# 99.net
KiCad netlist of a schematic drawn in EAGLE
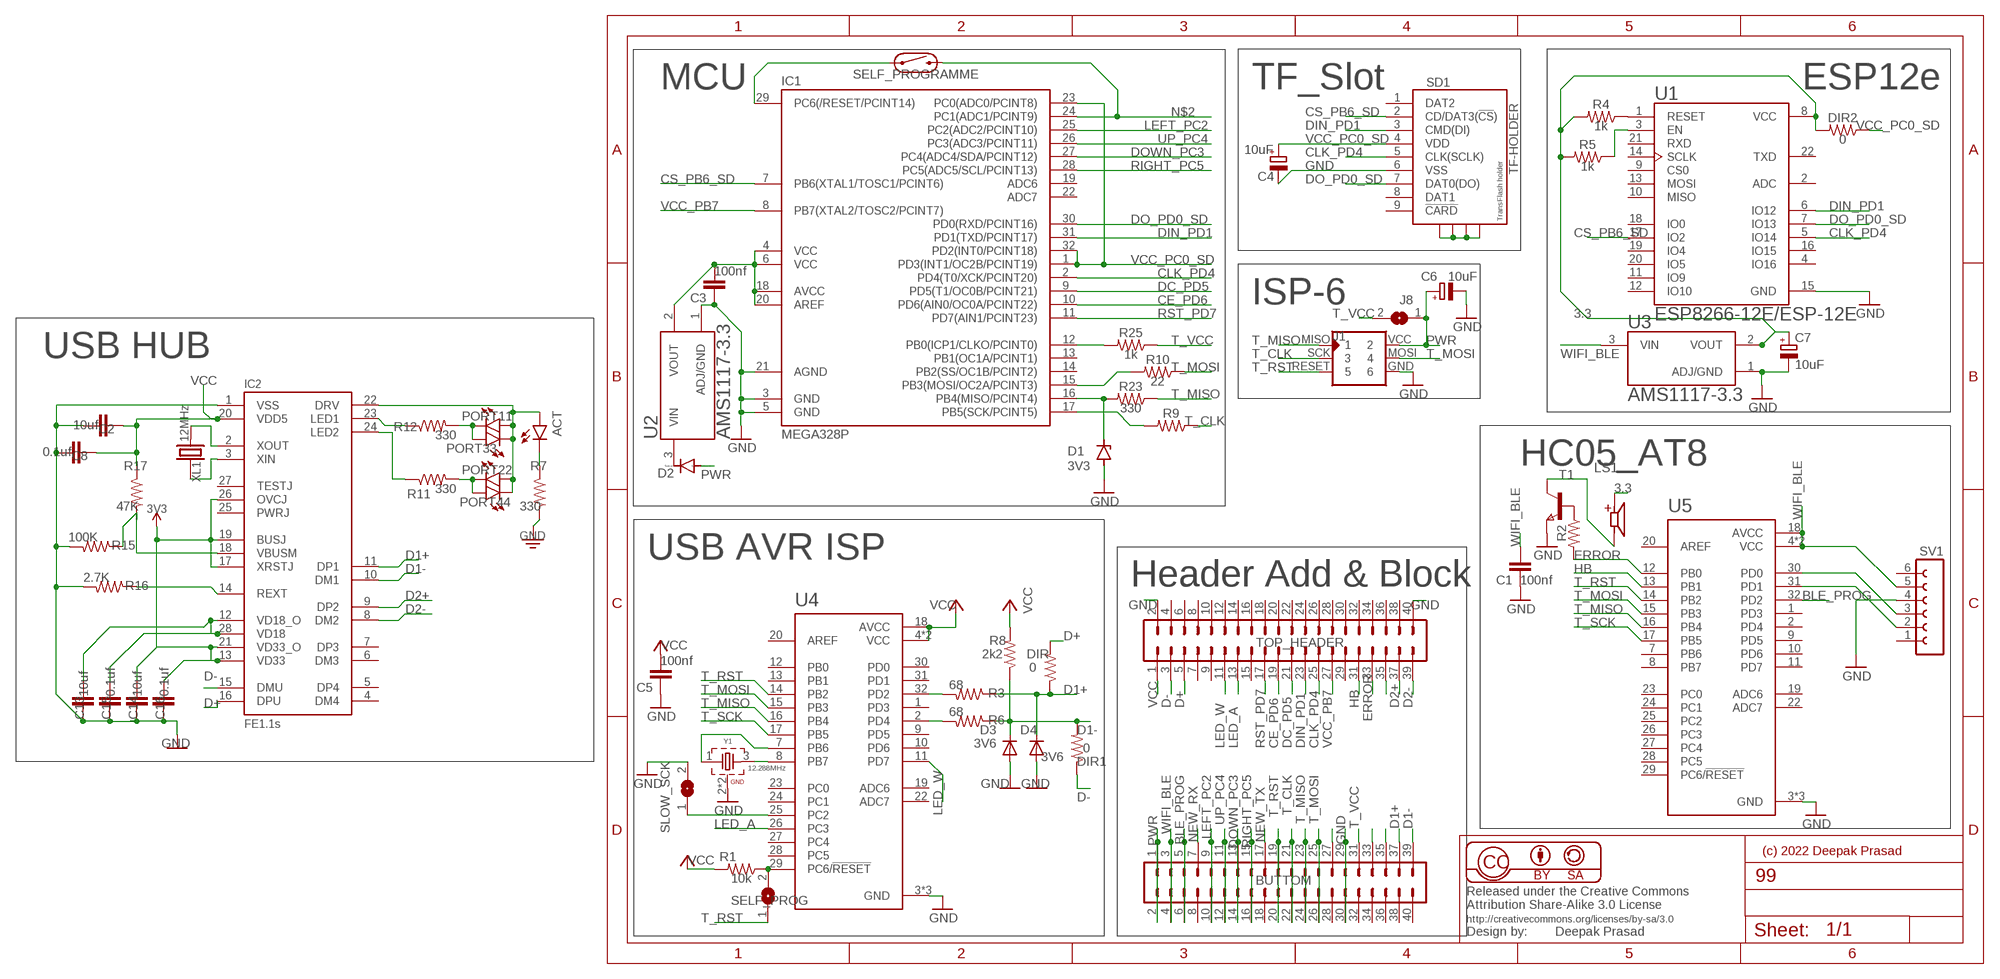
[diagram p0: schematic, sheet 1]

(export (version "E")
  (design (tool "Eeschema 10.0.6"))
  (components
    (comp (ref "ACT")
      (value "LED1206")
      (footprint "eagle-import:LED-1206")
      (libsource (lib "eagle-import") (part "LED1206"))
    )
    (comp (ref "BUTTOM")
      (value "MA20-2")
      (footprint "eagle-import:MA20-2")
      (libsource (lib "eagle-import") (part "MA20-2"))
    )
    (comp (ref "C1")
      (value "100nf")
      (footprint "eagle-import:C1206")
      (libsource (lib "eagle-import") (part "C-EUC1206"))
    )
    (comp (ref "C2")
      (value "10uf")
      (footprint "eagle-import:C1206")
      (libsource (lib "eagle-import") (part "C-EUC1206"))
    )
    (comp (ref "C3")
      (value "100nf")
      (footprint "eagle-import:C1206")
      (libsource (lib "eagle-import") (part "C-EUC1206"))
    )
    (comp (ref "C4")
      (value "10uF")
      (footprint "eagle-import:C_6032-28R")
      (libsource (lib "eagle-import") (part "CPOL-EUC/6032-28R"))
    )
    (comp (ref "C5")
      (value "100nf")
      (footprint "eagle-import:C1206")
      (libsource (lib "eagle-import") (part "C-EUC1206"))
    )
    (comp (ref "C6")
      (value "10uF")
      (footprint "eagle-import:C_6032-28R")
      (libsource (lib "eagle-import") (part "CPOL-EUC/6032-28R"))
    )
    (comp (ref "C7")
      (value "10uF")
      (footprint "eagle-import:C_6032-28R")
      (libsource (lib "eagle-import") (part "CPOL-EUC/6032-28R"))
    )
    (comp (ref "C8")
      (value "0.1uf")
      (footprint "eagle-import:C1206")
      (libsource (lib "eagle-import") (part "C-EUC1206"))
    )
    (comp (ref "C13")
      (value "10uf")
      (footprint "eagle-import:C1206")
      (libsource (lib "eagle-import") (part "C-EUC1206"))
    )
    (comp (ref "C14")
      (value "10uf")
      (footprint "eagle-import:C1206")
      (libsource (lib "eagle-import") (part "C-EUC1206"))
    )
    (comp (ref "C15")
      (value "0.1uf")
      (footprint "eagle-import:C1206")
      (libsource (lib "eagle-import") (part "C-EUC1206"))
    )
    (comp (ref "C16")
      (value "0.1uf")
      (footprint "eagle-import:C1206")
      (libsource (lib "eagle-import") (part "C-EUC1206"))
    )
    (comp (ref "D1")
      (value "3V3")
      (footprint "eagle-import:SOD80C")
      (libsource (lib "eagle-import") (part "ZENER-DIODESOD80C"))
    )
    (comp (ref "D2")
      (value "DIODE-DO214AC")
      (footprint "eagle-import:DO214AC")
      (libsource (lib "eagle-import") (part "DIODE-DO214AC"))
    )
    (comp (ref "D3")
      (value "3V6")
      (footprint "eagle-import:SMA-DIODE")
      (libsource (lib "eagle-import") (part "DIODESMA"))
    )
    (comp (ref "D4")
      (value "3V6")
      (footprint "eagle-import:SMA-DIODE")
      (libsource (lib "eagle-import") (part "DIODESMA"))
    )
    (comp (ref "DIR")
      (value "0")
      (footprint "eagle-import:RESC3216X70")
      (libsource (lib "eagle-import") (part "R-USCHIP-1206(3216-METRIC)_"))
    )
    (comp (ref "DIR1")
      (value "0")
      (footprint "eagle-import:RESC3216X70")
      (libsource (lib "eagle-import") (part "R-USCHIP-1206(3216-METRIC)_"))
    )
    (comp (ref "DIR2")
      (value "0")
      (footprint "eagle-import:RESC3216X70")
      (libsource (lib "eagle-import") (part "R-USCHIP-1206(3216-METRIC)_"))
    )
    (comp (ref "IC1")
      (value "MEGA328P")
      (footprint "eagle-import:TQFP32-08")
      (libsource (lib "eagle-import") (part "MEGA48/88/168-AU"))
    )
    (comp (ref "IC2")
      (value "FE1.1S")
      (footprint "eagle-import:FE1.1S_SSOP-28")
      (libsource (lib "eagle-import") (part "FE1.1S"))
    )
    (comp (ref "J1")
      (value "AVR-ISP-6PINAVR-ISP-6PIN")
      (footprint "eagle-import:AVR-ISP-6PIN")
      (libsource (lib "eagle-import") (part "AVR-ISP-6PINAVR-ISP-6PIN"))
    )
    (comp (ref "J8")
      (value "SJW")
      (footprint "eagle-import:SJW")
      (libsource (lib "eagle-import") (part "SJW"))
    )
    (comp (ref "LS1")
      (value "CMT-8530S-SMT")
      (footprint "eagle-import:CUI_CMT-8530S-SMT")
      (fields (field (name "MF") "CUI Devices") (field (name "MP") "CMT-8530S-SMT-TR"))
      (libsource (lib "eagle-import") (part "CMT-8530S-SMT"))
    )
    (comp (ref "PORT11")
      (value "LED1206")
      (footprint "eagle-import:LED-1206")
      (libsource (lib "eagle-import") (part "LED1206"))
    )
    (comp (ref "PORT22")
      (value "LED1206")
      (footprint "eagle-import:LED-1206")
      (libsource (lib "eagle-import") (part "LED1206"))
    )
    (comp (ref "PORT33")
      (value "LED1206")
      (footprint "eagle-import:LED-1206")
      (libsource (lib "eagle-import") (part "LED1206"))
    )
    (comp (ref "PORT44")
      (value "LED1206")
      (footprint "eagle-import:LED-1206")
      (libsource (lib "eagle-import") (part "LED1206"))
    )
    (comp (ref "R1")
      (value "10k")
      (footprint "eagle-import:RESC3216X70")
      (libsource (lib "eagle-import") (part "R-USCHIP-1206(3216-METRIC)_"))
    )
    (comp (ref "R2")
      (value "22")
      (footprint "eagle-import:RESC3216X70")
      (libsource (lib "eagle-import") (part "R-USCHIP-1206(3216-METRIC)_"))
    )
    (comp (ref "R3")
      (value "68")
      (footprint "eagle-import:RESC3216X70")
      (libsource (lib "eagle-import") (part "R-USCHIP-1206(3216-METRIC)_"))
    )
    (comp (ref "R4")
      (value "1k")
      (footprint "eagle-import:RESC3216X70")
      (libsource (lib "eagle-import") (part "R-USCHIP-1206(3216-METRIC)_"))
    )
    (comp (ref "R5")
      (value "1k")
      (footprint "eagle-import:RESC3216X70")
      (libsource (lib "eagle-import") (part "R-USCHIP-1206(3216-METRIC)_"))
    )
    (comp (ref "R6")
      (value "68")
      (footprint "eagle-import:RESC3216X70")
      (libsource (lib "eagle-import") (part "R-USCHIP-1206(3216-METRIC)_"))
    )
    (comp (ref "R7")
      (value "330")
      (footprint "eagle-import:RESC3216X70")
      (libsource (lib "eagle-import") (part "R-USCHIP-1206(3216-METRIC)_"))
    )
    (comp (ref "R8")
      (value "2k2")
      (footprint "eagle-import:RESC3216X70")
      (libsource (lib "eagle-import") (part "R-USCHIP-1206(3216-METRIC)_"))
    )
    (comp (ref "R9")
      (value "22")
      (footprint "eagle-import:RESC3216X70")
      (libsource (lib "eagle-import") (part "R-USCHIP-1206(3216-METRIC)_"))
    )
    (comp (ref "R10")
      (value "22")
      (footprint "eagle-import:RESC3216X70")
      (libsource (lib "eagle-import") (part "R-USCHIP-1206(3216-METRIC)_"))
    )
    (comp (ref "R11")
      (value "330")
      (footprint "eagle-import:RESC3216X70")
      (libsource (lib "eagle-import") (part "R-USCHIP-1206(3216-METRIC)_"))
    )
    (comp (ref "R12")
      (value "330")
      (footprint "eagle-import:RESC3216X70")
      (libsource (lib "eagle-import") (part "R-USCHIP-1206(3216-METRIC)_"))
    )
    (comp (ref "R15")
      (value "100K")
      (footprint "eagle-import:RESC3216X70")
      (libsource (lib "eagle-import") (part "R-USCHIP-1206(3216-METRIC)_"))
    )
    (comp (ref "R16")
      (value "2.7K")
      (footprint "eagle-import:RESC3216X70")
      (libsource (lib "eagle-import") (part "R-USCHIP-1206(3216-METRIC)_"))
    )
    (comp (ref "R17")
      (value "47K")
      (footprint "eagle-import:RESC3216X70")
      (libsource (lib "eagle-import") (part "R-USCHIP-1206(3216-METRIC)_"))
    )
    (comp (ref "R23")
      (value "330")
      (footprint "eagle-import:RESC3216X70")
      (libsource (lib "eagle-import") (part "R-USCHIP-1206(3216-METRIC)_"))
    )
    (comp (ref "R25")
      (value "1k")
      (footprint "eagle-import:RESC3216X70")
      (libsource (lib "eagle-import") (part "R-USCHIP-1206(3216-METRIC)_"))
    )
    (comp (ref "SD1")
      (value "TF-HOLDER")
      (footprint "eagle-import:TF-PULL")
      (libsource (lib "eagle-import") (part "TF-HOLDER"))
    )
    (comp (ref "SELF_PROG")
      (value "SJW")
      (footprint "eagle-import:SJW")
      (libsource (lib "eagle-import") (part "SJW"))
    )
    (comp (ref "SELF_PROGRAMME")
      (value "REED_SWITCH-PTH-GLASS")
      (footprint "eagle-import:REED_SWITCH_GLASS")
      (libsource (lib "eagle-import") (part "REED_SWITCH-PTH-GLASS"))
    )
    (comp (ref "SLOW_SCK")
      (value "SJW")
      (footprint "eagle-import:SJW")
      (libsource (lib "eagle-import") (part "SJW"))
    )
    (comp (ref "SV1")
      (value "FE06-1")
      (footprint "eagle-import:FE06")
      (libsource (lib "eagle-import") (part "FE06-1"))
    )
    (comp (ref "T1")
      (value "NPNSOT23")
      (footprint "eagle-import:SOT-23")
      (fields (field (name "MPN") "DSS20201L-7"))
      (libsource (lib "eagle-import") (part "NPNSOT23"))
    )
    (comp (ref "TOP_HEADER")
      (value "MA20-2")
      (footprint "eagle-import:MA20-2")
      (libsource (lib "eagle-import") (part "MA20-2"))
    )
    (comp (ref "U1")
      (value "ESP8266-12E/ESP-12E")
      (footprint "eagle-import:XCVR_ESP8266-12E_ESP-12E")
      (fields (field (name "MF") "AI-Thinker"))
      (libsource (lib "eagle-import") (part "ESP8266-12E/ESP-12E"))
    )
    (comp (ref "U2")
      (value "AMS1117-3.3")
      (footprint "eagle-import:SOT229P700X180-4N")
      (fields (field (name "MF") "Advanced Monolithic Systems"))
      (libsource (lib "eagle-import") (part "AMS1117-3.3"))
    )
    (comp (ref "U3")
      (value "AMS1117-3.3")
      (footprint "eagle-import:SOT229P700X180-4N")
      (fields (field (name "MF") "Advanced Monolithic Systems"))
      (libsource (lib "eagle-import") (part "AMS1117-3.3"))
    )
    (comp (ref "U4")
      (value "ATMEGA328P-AU")
      (footprint "eagle-import:QFP80P900X900X120-32N")
      (fields (field (name "MF") "Microchip Technology"))
      (libsource (lib "eagle-import") (part "ATMEGA328P-AU"))
    )
    (comp (ref "U5")
      (value "ATMEGA328P-AU")
      (footprint "eagle-import:QFP80P900X900X120-32N")
      (fields (field (name "MF") "Microchip Technology"))
      (libsource (lib "eagle-import") (part "ATMEGA328P-AU"))
    )
    (comp (ref "XL1")
      (value "12MHz")
      (footprint "eagle-import:HC49UP")
      (libsource (lib "eagle-import") (part "CRYSTALHC49UP"))
    )
    (comp (ref "Y1")
      (value "12.288MHz")
      (footprint "eagle-import:WE-XTAL_CFPX-104")
      (fields (field (name "TOLERANCE") "±20ppm"))
      (libsource (lib "eagle-import") (part "WE-XTAL_CFPX-104_830059523"))
    )
  )
  (nets
    (net (code "1") (name "/3.3") (class "Default")
      (node (ref "C7") (pin "+") (pinfunction "+_+") (pintype "passive"))
      (node (ref "DIR2") (pin "2") (pinfunction "2_2") (pintype "passive"))
      (node (ref "LS1") (pin "P") (pinfunction "P_P") (pintype "passive"))
      (node (ref "R4") (pin "2") (pinfunction "2_2") (pintype "passive"))
      (node (ref "R5") (pin "2") (pinfunction "2_2") (pintype "passive"))
      (node (ref "U1") (pin "8") (pinfunction "VCC_8") (pintype "power_in"))
      (node (ref "U3") (pin "2") (pinfunction "VOUT_2") (pintype "output"))
    )
    (net (code "2") (name "/BLE_PROG") (class "Default")
      (node (ref "BUTTOM") (pin "5") (pinfunction "5_5") (pintype "passive"))
      (node (ref "BUTTOM") (pin "6") (pinfunction "6_6") (pintype "passive"))
      (node (ref "U5") (pin "32") (pinfunction "PD2_32") (pintype "bidirectional"))
    )
    (net (code "3") (name "/CE_PD6") (class "Default")
      (node (ref "IC1") (pin "10") (pinfunction "PD6(AIN0/OC0A/PCINT22)_10") (pintype "bidirectional"))
      (node (ref "TOP_HEADER") (pin "19") (pinfunction "19_19") (pintype "passive"))
    )
    (net (code "4") (name "/CLK_PD4") (class "Default")
      (node (ref "IC1") (pin "2") (pinfunction "PD4(T0/XCK/PCINT20)_2") (pintype "bidirectional"))
      (node (ref "SD1") (pin "5") (pinfunction "CLK(SCLK)_5") (pintype "input"))
      (node (ref "TOP_HEADER") (pin "25") (pinfunction "25_25") (pintype "passive"))
      (node (ref "U1") (pin "5") (pinfunction "IO14_5") (pintype "bidirectional"))
    )
    (net (code "5") (name "/CS_PB6_SD") (class "Default")
      (node (ref "IC1") (pin "7") (pinfunction "PB6(XTAL1/TOSC1/PCINT6)_7") (pintype "bidirectional"))
      (node (ref "SD1") (pin "2") (pinfunction "CD/DAT3(~{CS})_2") (pintype "bidirectional"))
      (node (ref "U1") (pin "17") (pinfunction "IO2_17") (pintype "bidirectional"))
    )
    (net (code "6") (name "/D+") (class "Default")
      (node (ref "DIR") (pin "2") (pinfunction "2_2") (pintype "passive"))
      (node (ref "IC2") (pin "16") (pinfunction "DPU_16") (pintype "bidirectional"))
      (node (ref "TOP_HEADER") (pin "5") (pinfunction "5_5") (pintype "passive"))
    )
    (net (code "7") (name "/D-") (class "Default")
      (node (ref "DIR1") (pin "1") (pinfunction "1_1") (pintype "passive"))
      (node (ref "IC2") (pin "15") (pinfunction "DMU_15") (pintype "bidirectional"))
      (node (ref "TOP_HEADER") (pin "3") (pinfunction "3_3") (pintype "passive"))
    )
    (net (code "8") (name "/D1+") (class "Default")
      (node (ref "BUTTOM") (pin "37") (pinfunction "37_37") (pintype "passive"))
      (node (ref "D4") (pin "C") (pinfunction "C_C") (pintype "passive"))
      (node (ref "DIR") (pin "1") (pinfunction "1_1") (pintype "passive"))
      (node (ref "IC2") (pin "11") (pinfunction "DP1_11") (pintype "bidirectional"))
      (node (ref "R3") (pin "1") (pinfunction "1_1") (pintype "passive"))
    )
    (net (code "9") (name "/D1-") (class "Default")
      (node (ref "BUTTOM") (pin "39") (pinfunction "39_39") (pintype "passive"))
      (node (ref "D3") (pin "C") (pinfunction "C_C") (pintype "passive"))
      (node (ref "DIR1") (pin "2") (pinfunction "2_2") (pintype "passive"))
      (node (ref "IC2") (pin "10") (pinfunction "DM1_10") (pintype "bidirectional"))
      (node (ref "R6") (pin "1") (pinfunction "1_1") (pintype "passive"))
      (node (ref "R8") (pin "1") (pinfunction "1_1") (pintype "passive"))
    )
    (net (code "10") (name "/D2+") (class "Default")
      (node (ref "IC2") (pin "9") (pinfunction "DP2_9") (pintype "bidirectional"))
      (node (ref "TOP_HEADER") (pin "37") (pinfunction "37_37") (pintype "passive"))
    )
    (net (code "11") (name "/D2-") (class "Default")
      (node (ref "IC2") (pin "8") (pinfunction "DM2_8") (pintype "bidirectional"))
      (node (ref "TOP_HEADER") (pin "39") (pinfunction "39_39") (pintype "passive"))
    )
    (net (code "12") (name "/DC_PD5") (class "Default")
      (node (ref "IC1") (pin "9") (pinfunction "PD5(T1/OC0B/PCINT21)_9") (pintype "bidirectional"))
      (node (ref "TOP_HEADER") (pin "21") (pinfunction "21_21") (pintype "passive"))
    )
    (net (code "13") (name "/DIN_PD1") (class "Default")
      (node (ref "IC1") (pin "31") (pinfunction "PD1(TXD/PCINT17)_31") (pintype "bidirectional"))
      (node (ref "SD1") (pin "3") (pinfunction "CMD(DI)_3") (pintype "bidirectional"))
      (node (ref "TOP_HEADER") (pin "23") (pinfunction "23_23") (pintype "passive"))
      (node (ref "U1") (pin "6") (pinfunction "IO12_6") (pintype "bidirectional"))
    )
    (net (code "14") (name "/DOWN_PC3") (class "Default")
      (node (ref "BUTTOM") (pin "13") (pinfunction "13_13") (pintype "passive"))
      (node (ref "BUTTOM") (pin "14") (pinfunction "14_14") (pintype "passive"))
      (node (ref "IC1") (pin "27") (pinfunction "PC4(ADC4/SDA/PCINT12)_27") (pintype "bidirectional"))
    )
    (net (code "15") (name "/DO_PD0_SD") (class "Default")
      (node (ref "IC1") (pin "30") (pinfunction "PD0(RXD/PCINT16)_30") (pintype "bidirectional"))
      (node (ref "SD1") (pin "7") (pinfunction "DAT0(DO)_7") (pintype "bidirectional"))
      (node (ref "U1") (pin "7") (pinfunction "IO13_7") (pintype "bidirectional"))
    )
    (net (code "16") (name "/ERROR") (class "Default")
      (node (ref "R2") (pin "2") (pinfunction "2_2") (pintype "passive"))
      (node (ref "TOP_HEADER") (pin "33") (pinfunction "33_33") (pintype "passive"))
      (node (ref "U5") (pin "12") (pinfunction "PB0_12") (pintype "bidirectional"))
    )
    (net (code "17") (name "/HB") (class "Default")
      (node (ref "TOP_HEADER") (pin "31") (pinfunction "31_31") (pintype "passive"))
      (node (ref "U5") (pin "13") (pinfunction "PB1_13") (pintype "bidirectional"))
    )
    (net (code "18") (name "/LED_A") (class "Default")
      (node (ref "TOP_HEADER") (pin "13") (pinfunction "13_13") (pintype "passive"))
      (node (ref "U4") (pin "26") (pinfunction "PC3_26") (pintype "bidirectional"))
    )
    (net (code "19") (name "/LED_W") (class "Default")
      (node (ref "TOP_HEADER") (pin "11") (pinfunction "11_11") (pintype "passive"))
      (node (ref "U4") (pin "11") (pinfunction "PD7_11") (pintype "bidirectional"))
    )
    (net (code "20") (name "/LEFT_PC2") (class "Default")
      (node (ref "BUTTOM") (pin "10") (pinfunction "10_10") (pintype "passive"))
      (node (ref "BUTTOM") (pin "9") (pinfunction "9_9") (pintype "passive"))
      (node (ref "IC1") (pin "25") (pinfunction "PC2(ADC2/PCINT10)_25") (pintype "bidirectional"))
    )
    (net (code "21") (name "/N$2") (class "Default")
      (node (ref "IC1") (pin "24") (pinfunction "PC1(ADC1/PCINT9)_24") (pintype "bidirectional"))
      (node (ref "SELF_PROGRAMME") (pin "P$2") (pinfunction "2_P$2") (pintype "passive"))
    )
    (net (code "22") (name "/NEW_RX") (class "Default")
      (node (ref "BUTTOM") (pin "7") (pinfunction "7_7") (pintype "passive"))
    )
    (net (code "23") (name "/NEW_TX") (class "Default")
      (node (ref "BUTTOM") (pin "17") (pinfunction "17_17") (pintype "passive"))
    )
    (net (code "24") (name "/PWR") (class "Default")
      (node (ref "BUTTOM") (pin "1") (pinfunction "1_1") (pintype "passive"))
      (node (ref "BUTTOM") (pin "2") (pinfunction "2_2") (pintype "passive"))
      (node (ref "C6") (pin "+") (pinfunction "+_+") (pintype "passive"))
      (node (ref "D2") (pin "A") (pinfunction "A_A") (pintype "passive"))
      (node (ref "J1") (pin "VCC") (pinfunction "2_VCC") (pintype "passive"))
      (node (ref "J8") (pin "1") (pinfunction "1_1") (pintype "passive"))
    )
    (net (code "25") (name "/RIGHT_PC5") (class "Default")
      (node (ref "BUTTOM") (pin "15") (pinfunction "15_15") (pintype "passive"))
      (node (ref "BUTTOM") (pin "16") (pinfunction "16_16") (pintype "passive"))
      (node (ref "IC1") (pin "28") (pinfunction "PC5(ADC5/SCL/PCINT13)_28") (pintype "bidirectional"))
    )
    (net (code "26") (name "/RST_PD7") (class "Default")
      (node (ref "IC1") (pin "11") (pinfunction "PD7(AIN1/PCINT23)_11") (pintype "bidirectional"))
      (node (ref "TOP_HEADER") (pin "17") (pinfunction "17_17") (pintype "passive"))
    )
    (net (code "27") (name "/T_CLK") (class "Default")
      (node (ref "BUTTOM") (pin "21") (pinfunction "21_21") (pintype "passive"))
      (node (ref "BUTTOM") (pin "22") (pinfunction "22_22") (pintype "passive"))
      (node (ref "J1") (pin "SCK") (pinfunction "3_SCK") (pintype "passive"))
      (node (ref "R9") (pin "1") (pinfunction "1_1") (pintype "passive"))
    )
    (net (code "28") (name "/T_MISO") (class "Default")
      (node (ref "BUTTOM") (pin "23") (pinfunction "23_23") (pintype "passive"))
      (node (ref "BUTTOM") (pin "24") (pinfunction "24_24") (pintype "passive"))
      (node (ref "J1") (pin "MISO") (pinfunction "1_MISO") (pintype "passive"))
      (node (ref "R23") (pin "1") (pinfunction "1_1") (pintype "passive"))
      (node (ref "U4") (pin "16") (pinfunction "PB4_16") (pintype "bidirectional"))
      (node (ref "U5") (pin "16") (pinfunction "PB4_16") (pintype "bidirectional"))
    )
    (net (code "29") (name "/T_MOSI") (class "Default")
      (node (ref "BUTTOM") (pin "25") (pinfunction "25_25") (pintype "passive"))
      (node (ref "BUTTOM") (pin "26") (pinfunction "26_26") (pintype "passive"))
      (node (ref "J1") (pin "MOSI") (pinfunction "4_MOSI") (pintype "passive"))
      (node (ref "R10") (pin "1") (pinfunction "1_1") (pintype "passive"))
      (node (ref "U4") (pin "15") (pinfunction "PB3_15") (pintype "bidirectional"))
      (node (ref "U5") (pin "15") (pinfunction "PB3_15") (pintype "bidirectional"))
    )
    (net (code "30") (name "/T_RST") (class "Default")
      (node (ref "BUTTOM") (pin "19") (pinfunction "19_19") (pintype "passive"))
      (node (ref "BUTTOM") (pin "20") (pinfunction "20_20") (pintype "passive"))
      (node (ref "J1") (pin "RESET") (pinfunction "5_RESET") (pintype "passive"))
      (node (ref "SELF_PROG") (pin "1") (pinfunction "1_1") (pintype "passive"))
      (node (ref "U4") (pin "14") (pinfunction "PB2_14") (pintype "bidirectional"))
      (node (ref "U5") (pin "14") (pinfunction "PB2_14") (pintype "bidirectional"))
    )
    (net (code "31") (name "/T_SCK") (class "Default")
      (node (ref "U4") (pin "17") (pinfunction "PB5_17") (pintype "bidirectional"))
      (node (ref "U5") (pin "17") (pinfunction "PB5_17") (pintype "bidirectional"))
    )
    (net (code "32") (name "/T_VCC") (class "Default")
      (node (ref "BUTTOM") (pin "31") (pinfunction "31_31") (pintype "passive"))
      (node (ref "J8") (pin "2") (pinfunction "2_2") (pintype "passive"))
      (node (ref "R25") (pin "1") (pinfunction "1_1") (pintype "passive"))
    )
    (net (code "33") (name "/UP_PC4") (class "Default")
      (node (ref "BUTTOM") (pin "11") (pinfunction "11_11") (pintype "passive"))
      (node (ref "BUTTOM") (pin "12") (pinfunction "12_12") (pintype "passive"))
      (node (ref "IC1") (pin "26") (pinfunction "PC3(ADC3/PCINT11)_26") (pintype "bidirectional"))
    )
    (net (code "34") (name "/VCC_PB7") (class "Default")
      (node (ref "IC1") (pin "8") (pinfunction "PB7(XTAL2/TOSC2/PCINT7)_8") (pintype "bidirectional"))
      (node (ref "TOP_HEADER") (pin "27") (pinfunction "27_27") (pintype "passive"))
    )
    (net (code "35") (name "/VCC_PC0_SD") (class "Default")
      (node (ref "C4") (pin "+") (pinfunction "+_+") (pintype "passive"))
      (node (ref "DIR2") (pin "1") (pinfunction "1_1") (pintype "passive"))
      (node (ref "IC1") (pin "1") (pinfunction "PD3(INT1/OC2B/PCINT19)_1") (pintype "bidirectional"))
      (node (ref "IC1") (pin "23") (pinfunction "PC0(ADC0/PCINT8)_23") (pintype "bidirectional"))
      (node (ref "IC1") (pin "32") (pinfunction "PD2(INT0/PCINT18)_32") (pintype "bidirectional"))
      (node (ref "SD1") (pin "4") (pinfunction "VDD_4") (pintype "power_in"))
    )
    (net (code "36") (name "/WIFI_BLE") (class "Default")
      (node (ref "BUTTOM") (pin "3") (pinfunction "3_3") (pintype "passive"))
      (node (ref "BUTTOM") (pin "4") (pinfunction "4_4") (pintype "passive"))
      (node (ref "C1") (pin "2") (pinfunction "2_2") (pintype "passive"))
      (node (ref "SV1") (pin "5") (pinfunction "5_5") (pintype "passive"))
      (node (ref "U3") (pin "3") (pinfunction "VIN_3") (pintype "input"))
      (node (ref "U5") (pin "18") (pinfunction "AVCC_18") (pintype "power_in"))
      (node (ref "U5") (pin "4") (pinfunction "VCC_4") (pintype "power_in"))
      (node (ref "U5") (pin "6") (pinfunction "VCC_6") (pintype "power_in"))
    )
    (net (code "37") (name "3V3") (class "Default")
      (node (ref "C14") (pin "2") (pinfunction "2_2") (pintype "passive"))
      (node (ref "C16") (pin "2") (pinfunction "2_2") (pintype "passive"))
      (node (ref "IC2") (pin "13") (pinfunction "VD33_13") (pintype "bidirectional"))
      (node (ref "IC2") (pin "17") (pinfunction "XRSTJ_17") (pintype "bidirectional"))
      (node (ref "IC2") (pin "19") (pinfunction "BUSJ_19") (pintype "bidirectional"))
      (node (ref "IC2") (pin "21") (pinfunction "VD33_O_21") (pintype "bidirectional"))
      (node (ref "IC2") (pin "26") (pinfunction "OVCJ_26") (pintype "bidirectional"))
    )
    (net (code "38") (name "GND") (class "Default")
      (node (ref "BUTTOM") (pin "29") (pinfunction "29_29") (pintype "passive"))
      (node (ref "BUTTOM") (pin "30") (pinfunction "30_30") (pintype "passive"))
      (node (ref "C1") (pin "1") (pinfunction "1_1") (pintype "passive"))
      (node (ref "C13") (pin "1") (pinfunction "1_1") (pintype "passive"))
      (node (ref "C14") (pin "1") (pinfunction "1_1") (pintype "passive"))
      (node (ref "C15") (pin "1") (pinfunction "1_1") (pintype "passive"))
      (node (ref "C16") (pin "1") (pinfunction "1_1") (pintype "passive"))
      (node (ref "C2") (pin "2") (pinfunction "2_2") (pintype "passive"))
      (node (ref "C3") (pin "1") (pinfunction "1_1") (pintype "passive"))
      (node (ref "C4") (pin "-") (pinfunction "-_-") (pintype "passive"))
      (node (ref "C5") (pin "1") (pinfunction "1_1") (pintype "passive"))
      (node (ref "C6") (pin "-") (pinfunction "-_-") (pintype "passive"))
      (node (ref "C7") (pin "-") (pinfunction "-_-") (pintype "passive"))
      (node (ref "C8") (pin "2") (pinfunction "2_2") (pintype "passive"))
      (node (ref "D1") (pin "A") (pinfunction "A_A") (pintype "passive"))
      (node (ref "D3") (pin "A") (pinfunction "A_A") (pintype "passive"))
      (node (ref "D4") (pin "A") (pinfunction "A_A") (pintype "passive"))
      (node (ref "IC1") (pin "21") (pinfunction "AGND_21") (pintype "power_in"))
      (node (ref "IC1") (pin "3") (pinfunction "GND_3") (pintype "power_in"))
      (node (ref "IC1") (pin "5") (pinfunction "GND_5") (pintype "power_in"))
      (node (ref "IC2") (pin "1") (pinfunction "VSS_1") (pintype "bidirectional"))
      (node (ref "J1") (pin "GND") (pinfunction "6_GND") (pintype "passive"))
      (node (ref "R15") (pin "2") (pinfunction "2_2") (pintype "passive"))
      (node (ref "R16") (pin "2") (pinfunction "2_2") (pintype "passive"))
      (node (ref "R7") (pin "2") (pinfunction "2_2") (pintype "passive"))
      (node (ref "SD1") (pin "6") (pinfunction "VSS_6") (pintype "power_in"))
      (node (ref "SLOW_SCK") (pin "2") (pinfunction "2_2") (pintype "passive"))
      (node (ref "SV1") (pin "4") (pinfunction "4_4") (pintype "passive"))
      (node (ref "T1") (pin "2") (pinfunction "E_2") (pintype "passive"))
      (node (ref "TOP_HEADER") (pin "2") (pinfunction "2_2") (pintype "passive"))
      (node (ref "TOP_HEADER") (pin "40") (pinfunction "40_40") (pintype "passive"))
      (node (ref "U1") (pin "15") (pinfunction "GND_15") (pintype "power_in"))
      (node (ref "U2") (pin "1") (pinfunction "ADJ/GND_1") (pintype "power_in"))
      (node (ref "U3") (pin "1") (pinfunction "ADJ/GND_1") (pintype "power_in"))
      (node (ref "U4") (pin "21") (pinfunction "GND_21") (pintype "power_in"))
      (node (ref "U4") (pin "3") (pinfunction "GND_3") (pintype "power_in"))
      (node (ref "U4") (pin "5") (pinfunction "GND_5") (pintype "power_in"))
      (node (ref "U5") (pin "21") (pinfunction "GND_21") (pintype "power_in"))
      (node (ref "U5") (pin "3") (pinfunction "GND_3") (pintype "power_in"))
      (node (ref "U5") (pin "5") (pinfunction "GND_5") (pintype "power_in"))
      (node (ref "Y1") (pin "2") (pinfunction "GND_2") (pintype "passive"))
      (node (ref "Y1") (pin "4") (pinfunction "GND_4") (pintype "passive"))
    )
    (net (code "39") (name "Net-(ACT-PadC)") (class "Default")
      (node (ref "ACT") (pin "C") (pinfunction "C_C") (pintype "passive"))
      (node (ref "R7") (pin "1") (pinfunction "1_1") (pintype "passive"))
    )
    (net (code "40") (name "Net-(IC1-AREF)") (class "Default")
      (node (ref "C3") (pin "2") (pinfunction "2_2") (pintype "passive"))
      (node (ref "IC1") (pin "18") (pinfunction "AVCC_18") (pintype "passive"))
      (node (ref "IC1") (pin "20") (pinfunction "AREF_20") (pintype "passive"))
      (node (ref "IC1") (pin "4") (pinfunction "VCC_4") (pintype "power_in"))
      (node (ref "IC1") (pin "6") (pinfunction "VCC_6") (pintype "power_in"))
      (node (ref "U2") (pin "2") (pinfunction "VOUT_2") (pintype "output"))
    )
    (net (code "41") (name "Net-(IC1-PB0(ICP1{slash}CLKO{slash}PCINT0))") (class "Default")
      (node (ref "IC1") (pin "12") (pinfunction "PB0(ICP1/CLKO/PCINT0)_12") (pintype "bidirectional"))
      (node (ref "R25") (pin "2") (pinfunction "2_2") (pintype "passive"))
    )
    (net (code "42") (name "Net-(IC1-PB3(MOSI{slash}OC2A{slash}PCINT3))") (class "Default")
      (node (ref "IC1") (pin "15") (pinfunction "PB3(MOSI/OC2A/PCINT3)_15") (pintype "bidirectional"))
      (node (ref "R10") (pin "2") (pinfunction "2_2") (pintype "passive"))
    )
    (net (code "43") (name "Net-(IC1-PB4(MISO{slash}PCINT4))") (class "Default")
      (node (ref "D1") (pin "C") (pinfunction "C_C") (pintype "passive"))
      (node (ref "IC1") (pin "16") (pinfunction "PB4(MISO/PCINT4)_16") (pintype "bidirectional"))
      (node (ref "R23") (pin "2") (pinfunction "2_2") (pintype "passive"))
    )
    (net (code "44") (name "Net-(IC1-PB5(SCK{slash}PCINT5))") (class "Default")
      (node (ref "IC1") (pin "17") (pinfunction "PB5(SCK/PCINT5)_17") (pintype "bidirectional"))
      (node (ref "R9") (pin "2") (pinfunction "2_2") (pintype "passive"))
    )
    (net (code "45") (name "Net-(IC1-PC6({slash}RESET{slash}PCINT14))") (class "Default")
      (node (ref "IC1") (pin "29") (pinfunction "PC6(/RESET/PCINT14)_29") (pintype "bidirectional"))
      (node (ref "SELF_PROGRAMME") (pin "P$1") (pinfunction "1_P$1") (pintype "passive"))
    )
    (net (code "46") (name "Net-(IC2-DRV)") (class "Default")
      (node (ref "ACT") (pin "A") (pinfunction "A_A") (pintype "passive"))
      (node (ref "IC2") (pin "22") (pinfunction "DRV_22") (pintype "bidirectional"))
      (node (ref "PORT11") (pin "A") (pinfunction "A_A") (pintype "passive"))
      (node (ref "PORT22") (pin "A") (pinfunction "A_A") (pintype "passive"))
      (node (ref "PORT33") (pin "C") (pinfunction "C_C") (pintype "passive"))
      (node (ref "PORT44") (pin "C") (pinfunction "C_C") (pintype "passive"))
    )
    (net (code "47") (name "Net-(IC2-LED1)") (class "Default")
      (node (ref "IC2") (pin "23") (pinfunction "LED1_23") (pintype "bidirectional"))
      (node (ref "R12") (pin "1") (pinfunction "1_1") (pintype "passive"))
    )
    (net (code "48") (name "Net-(IC2-LED2)") (class "Default")
      (node (ref "IC2") (pin "24") (pinfunction "LED2_24") (pintype "bidirectional"))
      (node (ref "R11") (pin "1") (pinfunction "1_1") (pintype "passive"))
    )
    (net (code "49") (name "Net-(IC2-REXT)") (class "Default")
      (node (ref "IC2") (pin "14") (pinfunction "REXT_14") (pintype "bidirectional"))
      (node (ref "R16") (pin "1") (pinfunction "1_1") (pintype "passive"))
    )
    (net (code "50") (name "Net-(IC2-VBUSM)") (class "Default")
      (node (ref "IC2") (pin "18") (pinfunction "VBUSM_18") (pintype "bidirectional"))
      (node (ref "R15") (pin "1") (pinfunction "1_1") (pintype "passive"))
      (node (ref "R17") (pin "2") (pinfunction "2_2") (pintype "passive"))
    )
    (net (code "51") (name "Net-(IC2-VD18)") (class "Default")
      (node (ref "C13") (pin "2") (pinfunction "2_2") (pintype "passive"))
      (node (ref "C15") (pin "2") (pinfunction "2_2") (pintype "passive"))
      (node (ref "IC2") (pin "12") (pinfunction "VD18_O_12") (pintype "bidirectional"))
      (node (ref "IC2") (pin "28") (pinfunction "VD18_28") (pintype "bidirectional"))
    )
    (net (code "52") (name "Net-(IC2-XIN)") (class "Default")
      (node (ref "IC2") (pin "3") (pinfunction "XIN_3") (pintype "bidirectional"))
      (node (ref "XL1") (pin "1") (pinfunction "1_1") (pintype "passive"))
    )
    (net (code "53") (name "Net-(IC2-XOUT)") (class "Default")
      (node (ref "IC2") (pin "2") (pinfunction "XOUT_2") (pintype "bidirectional"))
      (node (ref "XL1") (pin "2") (pinfunction "2_2") (pintype "passive"))
    )
    (net (code "54") (name "Net-(PORT11-PadC)") (class "Default")
      (node (ref "PORT11") (pin "C") (pinfunction "C_C") (pintype "passive"))
      (node (ref "PORT33") (pin "A") (pinfunction "A_A") (pintype "passive"))
      (node (ref "R12") (pin "2") (pinfunction "2_2") (pintype "passive"))
    )
    (net (code "55") (name "Net-(PORT22-PadC)") (class "Default")
      (node (ref "PORT22") (pin "C") (pinfunction "C_C") (pintype "passive"))
      (node (ref "PORT44") (pin "A") (pinfunction "A_A") (pintype "passive"))
      (node (ref "R11") (pin "2") (pinfunction "2_2") (pintype "passive"))
    )
    (net (code "56") (name "Net-(SD1-PadS1)") (class "Default")
      (node (ref "SD1") (pin "S1") (pinfunction "S1_S1") (pintype "passive"))
      (node (ref "SD1") (pin "S2") (pinfunction "S2_S2") (pintype "passive"))
      (node (ref "SD1") (pin "S3") (pinfunction "S3_S3") (pintype "passive"))
      (node (ref "SD1") (pin "S4") (pinfunction "S4_S4") (pintype "passive"))
    )
    (net (code "57") (name "Net-(T1-B)") (class "Default")
      (node (ref "R2") (pin "1") (pinfunction "1_1") (pintype "passive"))
      (node (ref "T1") (pin "3") (pinfunction "B_3") (pintype "passive"))
    )
    (net (code "58") (name "Net-(T1-C)") (class "Default")
      (node (ref "LS1") (pin "N") (pinfunction "N_N") (pintype "passive"))
      (node (ref "T1") (pin "1") (pinfunction "C_1") (pintype "passive"))
    )
    (net (code "59") (name "Net-(U1-EN)") (class "Default")
      (node (ref "R5") (pin "1") (pinfunction "1_1") (pintype "passive"))
      (node (ref "U1") (pin "3") (pinfunction "EN_3") (pintype "input"))
    )
    (net (code "60") (name "Net-(U1-RESET)") (class "Default")
      (node (ref "R4") (pin "1") (pinfunction "1_1") (pintype "passive"))
      (node (ref "U1") (pin "1") (pinfunction "RESET_1") (pintype "input"))
    )
    (net (code "61") (name "Net-(U2-VIN)") (class "Default")
      (node (ref "D2") (pin "C") (pinfunction "C_C") (pintype "passive"))
      (node (ref "U2") (pin "3") (pinfunction "VIN_3") (pintype "input"))
    )
    (net (code "62") (name "Net-(U4-PB6)") (class "Default")
      (node (ref "U4") (pin "7") (pinfunction "PB6_7") (pintype "bidirectional"))
      (node (ref "Y1") (pin "1") (pinfunction "1_1") (pintype "passive"))
    )
    (net (code "63") (name "Net-(U4-PB7)") (class "Default")
      (node (ref "U4") (pin "8") (pinfunction "PB7_8") (pintype "bidirectional"))
      (node (ref "Y1") (pin "3") (pinfunction "2_3") (pintype "passive"))
    )
    (net (code "64") (name "Net-(U4-PC2)") (class "Default")
      (node (ref "SLOW_SCK") (pin "1") (pinfunction "1_1") (pintype "passive"))
      (node (ref "U4") (pin "25") (pinfunction "PC2_25") (pintype "bidirectional"))
    )
    (net (code "65") (name "Net-(U4-PC6{slash}~{RESET})") (class "Default")
      (node (ref "R1") (pin "1") (pinfunction "1_1") (pintype "passive"))
      (node (ref "SELF_PROG") (pin "2") (pinfunction "2_2") (pintype "passive"))
      (node (ref "U4") (pin "29") (pinfunction "PC6/~{RESET}_29") (pintype "bidirectional"))
    )
    (net (code "66") (name "Net-(U4-PD2)") (class "Default")
      (node (ref "R3") (pin "2") (pinfunction "2_2") (pintype "passive"))
      (node (ref "U4") (pin "32") (pinfunction "PD2_32") (pintype "bidirectional"))
    )
    (net (code "67") (name "Net-(U4-PD4)") (class "Default")
      (node (ref "R6") (pin "2") (pinfunction "2_2") (pintype "passive"))
      (node (ref "U4") (pin "2") (pinfunction "PD4_2") (pintype "bidirectional"))
    )
    (net (code "68") (name "Net-(U5-PD0)") (class "Default")
      (node (ref "SV1") (pin "3") (pinfunction "3_3") (pintype "passive"))
      (node (ref "U5") (pin "30") (pinfunction "PD0_30") (pintype "bidirectional"))
    )
    (net (code "69") (name "Net-(U5-PD1)") (class "Default")
      (node (ref "SV1") (pin "2") (pinfunction "2_2") (pintype "passive"))
      (node (ref "U5") (pin "31") (pinfunction "PD1_31") (pintype "bidirectional"))
    )
    (net (code "70") (name "VCC") (class "Default")
      (node (ref "C2") (pin "1") (pinfunction "1_1") (pintype "passive"))
      (node (ref "C5") (pin "2") (pinfunction "2_2") (pintype "passive"))
      (node (ref "C8") (pin "1") (pinfunction "1_1") (pintype "passive"))
      (node (ref "IC2") (pin "20") (pinfunction "VDD5_20") (pintype "bidirectional"))
      (node (ref "R1") (pin "2") (pinfunction "2_2") (pintype "passive"))
      (node (ref "R17") (pin "1") (pinfunction "1_1") (pintype "passive"))
      (node (ref "R8") (pin "2") (pinfunction "2_2") (pintype "passive"))
      (node (ref "TOP_HEADER") (pin "1") (pinfunction "1_1") (pintype "passive"))
      (node (ref "U4") (pin "18") (pinfunction "AVCC_18") (pintype "power_in"))
      (node (ref "U4") (pin "4") (pinfunction "VCC_4") (pintype "power_in"))
      (node (ref "U4") (pin "6") (pinfunction "VCC_6") (pintype "power_in"))
    )
    (net (code "71") (name "unconnected-(BUTTOM-Pad8)") (class "Default")
      (node (ref "BUTTOM") (pin "8") (pinfunction "8_8") (pintype "passive"))
    )
    (net (code "72") (name "unconnected-(BUTTOM-Pad18)") (class "Default")
      (node (ref "BUTTOM") (pin "18") (pinfunction "18_18") (pintype "passive"))
    )
    (net (code "73") (name "unconnected-(BUTTOM-Pad27)") (class "Default")
      (node (ref "BUTTOM") (pin "27") (pinfunction "27_27") (pintype "passive"))
    )
    (net (code "74") (name "unconnected-(BUTTOM-Pad28)") (class "Default")
      (node (ref "BUTTOM") (pin "28") (pinfunction "28_28") (pintype "passive"))
    )
    (net (code "75") (name "unconnected-(BUTTOM-Pad32)") (class "Default")
      (node (ref "BUTTOM") (pin "32") (pinfunction "32_32") (pintype "passive"))
    )
    (net (code "76") (name "unconnected-(BUTTOM-Pad33)") (class "Default")
      (node (ref "BUTTOM") (pin "33") (pinfunction "33_33") (pintype "passive"))
    )
    (net (code "77") (name "unconnected-(BUTTOM-Pad34)") (class "Default")
      (node (ref "BUTTOM") (pin "34") (pinfunction "34_34") (pintype "passive"))
    )
    (net (code "78") (name "unconnected-(BUTTOM-Pad35)") (class "Default")
      (node (ref "BUTTOM") (pin "35") (pinfunction "35_35") (pintype "passive"))
    )
    (net (code "79") (name "unconnected-(BUTTOM-Pad36)") (class "Default")
      (node (ref "BUTTOM") (pin "36") (pinfunction "36_36") (pintype "passive"))
    )
    (net (code "80") (name "unconnected-(BUTTOM-Pad38)") (class "Default")
      (node (ref "BUTTOM") (pin "38") (pinfunction "38_38") (pintype "passive"))
    )
    (net (code "81") (name "unconnected-(BUTTOM-Pad40)") (class "Default")
      (node (ref "BUTTOM") (pin "40") (pinfunction "40_40") (pintype "passive"))
    )
    (net (code "82") (name "unconnected-(IC1-ADC6-Pad19)") (class "Default")
      (node (ref "IC1") (pin "19") (pinfunction "ADC6_19") (pintype "passive"))
    )
    (net (code "83") (name "unconnected-(IC1-ADC7-Pad22)") (class "Default")
      (node (ref "IC1") (pin "22") (pinfunction "ADC7_22") (pintype "passive"))
    )
    (net (code "84") (name "unconnected-(IC1-PB1(OC1A{slash}PCINT1)-Pad13)") (class "Default")
      (node (ref "IC1") (pin "13") (pinfunction "PB1(OC1A/PCINT1)_13") (pintype "bidirectional"))
    )
    (net (code "85") (name "unconnected-(IC1-PB2(SS{slash}OC1B{slash}PCINT2)-Pad14)") (class "Default")
      (node (ref "IC1") (pin "14") (pinfunction "PB2(SS/OC1B/PCINT2)_14") (pintype "bidirectional"))
    )
    (net (code "86") (name "unconnected-(IC2-DM3-Pad6)") (class "Default")
      (node (ref "IC2") (pin "6") (pinfunction "DM3_6") (pintype "bidirectional"))
    )
    (net (code "87") (name "unconnected-(IC2-DM4-Pad4)") (class "Default")
      (node (ref "IC2") (pin "4") (pinfunction "DM4_4") (pintype "bidirectional"))
    )
    (net (code "88") (name "unconnected-(IC2-DP3-Pad7)") (class "Default")
      (node (ref "IC2") (pin "7") (pinfunction "DP3_7") (pintype "bidirectional"))
    )
    (net (code "89") (name "unconnected-(IC2-DP4-Pad5)") (class "Default")
      (node (ref "IC2") (pin "5") (pinfunction "DP4_5") (pintype "bidirectional"))
    )
    (net (code "90") (name "unconnected-(IC2-PWRJ-Pad25)") (class "Default")
      (node (ref "IC2") (pin "25") (pinfunction "PWRJ_25") (pintype "bidirectional"))
    )
    (net (code "91") (name "unconnected-(IC2-TESTJ-Pad27)") (class "Default")
      (node (ref "IC2") (pin "27") (pinfunction "TESTJ_27") (pintype "bidirectional"))
    )
    (net (code "92") (name "unconnected-(SD1-DAT1-Pad8)") (class "Default")
      (node (ref "SD1") (pin "8") (pinfunction "DAT1_8") (pintype "bidirectional"))
    )
    (net (code "93") (name "unconnected-(SD1-DAT2-Pad1)") (class "Default")
      (node (ref "SD1") (pin "1") (pinfunction "DAT2_1") (pintype "bidirectional"))
    )
    (net (code "94") (name "unconnected-(SD1-~{CARD}-Pad9)") (class "Default")
      (node (ref "SD1") (pin "9") (pinfunction "~{CARD}_9") (pintype "passive"))
    )
    (net (code "95") (name "unconnected-(SV1-Pad1)") (class "Default")
      (node (ref "SV1") (pin "1") (pinfunction "1_1") (pintype "passive"))
    )
    (net (code "96") (name "unconnected-(SV1-Pad6)") (class "Default")
      (node (ref "SV1") (pin "6") (pinfunction "6_6") (pintype "passive"))
    )
    (net (code "97") (name "unconnected-(TOP_HEADER-Pad4)") (class "Default")
      (node (ref "TOP_HEADER") (pin "4") (pinfunction "4_4") (pintype "passive"))
    )
    (net (code "98") (name "unconnected-(TOP_HEADER-Pad6)") (class "Default")
      (node (ref "TOP_HEADER") (pin "6") (pinfunction "6_6") (pintype "passive"))
    )
    (net (code "99") (name "unconnected-(TOP_HEADER-Pad7)") (class "Default")
      (node (ref "TOP_HEADER") (pin "7") (pinfunction "7_7") (pintype "passive"))
    )
    (net (code "100") (name "unconnected-(TOP_HEADER-Pad8)") (class "Default")
      (node (ref "TOP_HEADER") (pin "8") (pinfunction "8_8") (pintype "passive"))
    )
    (net (code "101") (name "unconnected-(TOP_HEADER-Pad9)") (class "Default")
      (node (ref "TOP_HEADER") (pin "9") (pinfunction "9_9") (pintype "passive"))
    )
    (net (code "102") (name "unconnected-(TOP_HEADER-Pad10)") (class "Default")
      (node (ref "TOP_HEADER") (pin "10") (pinfunction "10_10") (pintype "passive"))
    )
    (net (code "103") (name "unconnected-(TOP_HEADER-Pad12)") (class "Default")
      (node (ref "TOP_HEADER") (pin "12") (pinfunction "12_12") (pintype "passive"))
    )
    (net (code "104") (name "unconnected-(TOP_HEADER-Pad14)") (class "Default")
      (node (ref "TOP_HEADER") (pin "14") (pinfunction "14_14") (pintype "passive"))
    )
    (net (code "105") (name "unconnected-(TOP_HEADER-Pad15)") (class "Default")
      (node (ref "TOP_HEADER") (pin "15") (pinfunction "15_15") (pintype "passive"))
    )
    (net (code "106") (name "unconnected-(TOP_HEADER-Pad16)") (class "Default")
      (node (ref "TOP_HEADER") (pin "16") (pinfunction "16_16") (pintype "passive"))
    )
    (net (code "107") (name "unconnected-(TOP_HEADER-Pad18)") (class "Default")
      (node (ref "TOP_HEADER") (pin "18") (pinfunction "18_18") (pintype "passive"))
    )
    (net (code "108") (name "unconnected-(TOP_HEADER-Pad20)") (class "Default")
      (node (ref "TOP_HEADER") (pin "20") (pinfunction "20_20") (pintype "passive"))
    )
    (net (code "109") (name "unconnected-(TOP_HEADER-Pad22)") (class "Default")
      (node (ref "TOP_HEADER") (pin "22") (pinfunction "22_22") (pintype "passive"))
    )
    (net (code "110") (name "unconnected-(TOP_HEADER-Pad24)") (class "Default")
      (node (ref "TOP_HEADER") (pin "24") (pinfunction "24_24") (pintype "passive"))
    )
    (net (code "111") (name "unconnected-(TOP_HEADER-Pad26)") (class "Default")
      (node (ref "TOP_HEADER") (pin "26") (pinfunction "26_26") (pintype "passive"))
    )
    (net (code "112") (name "unconnected-(TOP_HEADER-Pad28)") (class "Default")
      (node (ref "TOP_HEADER") (pin "28") (pinfunction "28_28") (pintype "passive"))
    )
    (net (code "113") (name "unconnected-(TOP_HEADER-Pad29)") (class "Default")
      (node (ref "TOP_HEADER") (pin "29") (pinfunction "29_29") (pintype "passive"))
    )
    (net (code "114") (name "unconnected-(TOP_HEADER-Pad30)") (class "Default")
      (node (ref "TOP_HEADER") (pin "30") (pinfunction "30_30") (pintype "passive"))
    )
    (net (code "115") (name "unconnected-(TOP_HEADER-Pad32)") (class "Default")
      (node (ref "TOP_HEADER") (pin "32") (pinfunction "32_32") (pintype "passive"))
    )
    (net (code "116") (name "unconnected-(TOP_HEADER-Pad34)") (class "Default")
      (node (ref "TOP_HEADER") (pin "34") (pinfunction "34_34") (pintype "passive"))
    )
    (net (code "117") (name "unconnected-(TOP_HEADER-Pad35)") (class "Default")
      (node (ref "TOP_HEADER") (pin "35") (pinfunction "35_35") (pintype "passive"))
    )
    (net (code "118") (name "unconnected-(TOP_HEADER-Pad36)") (class "Default")
      (node (ref "TOP_HEADER") (pin "36") (pinfunction "36_36") (pintype "passive"))
    )
    (net (code "119") (name "unconnected-(TOP_HEADER-Pad38)") (class "Default")
      (node (ref "TOP_HEADER") (pin "38") (pinfunction "38_38") (pintype "passive"))
    )
    (net (code "120") (name "unconnected-(U1-ADC-Pad2)") (class "Default")
      (node (ref "U1") (pin "2") (pinfunction "ADC_2") (pintype "passive"))
    )
    (net (code "121") (name "unconnected-(U1-CS0-Pad9)") (class "Default")
      (node (ref "U1") (pin "9") (pinfunction "CS0_9") (pintype "input"))
    )
    (net (code "122") (name "unconnected-(U1-IO0-Pad18)") (class "Default")
      (node (ref "U1") (pin "18") (pinfunction "IO0_18") (pintype "bidirectional"))
    )
    (net (code "123") (name "unconnected-(U1-IO4-Pad19)") (class "Default")
      (node (ref "U1") (pin "19") (pinfunction "IO4_19") (pintype "bidirectional"))
    )
    (net (code "124") (name "unconnected-(U1-IO5-Pad20)") (class "Default")
      (node (ref "U1") (pin "20") (pinfunction "IO5_20") (pintype "bidirectional"))
    )
    (net (code "125") (name "unconnected-(U1-IO9-Pad11)") (class "Default")
      (node (ref "U1") (pin "11") (pinfunction "IO9_11") (pintype "bidirectional"))
    )
    (net (code "126") (name "unconnected-(U1-IO10-Pad12)") (class "Default")
      (node (ref "U1") (pin "12") (pinfunction "IO10_12") (pintype "bidirectional"))
    )
    (net (code "127") (name "unconnected-(U1-IO15-Pad16)") (class "Default")
      (node (ref "U1") (pin "16") (pinfunction "IO15_16") (pintype "bidirectional"))
    )
    (net (code "128") (name "unconnected-(U1-IO16-Pad4)") (class "Default")
      (node (ref "U1") (pin "4") (pinfunction "IO16_4") (pintype "bidirectional"))
    )
    (net (code "129") (name "unconnected-(U1-MISO-Pad10)") (class "Default")
      (node (ref "U1") (pin "10") (pinfunction "MISO_10") (pintype "bidirectional"))
    )
    (net (code "130") (name "unconnected-(U1-MOSI-Pad13)") (class "Default")
      (node (ref "U1") (pin "13") (pinfunction "MOSI_13") (pintype "bidirectional"))
    )
    (net (code "131") (name "unconnected-(U1-RXD-Pad21)") (class "Default")
      (node (ref "U1") (pin "21") (pinfunction "RXD_21") (pintype "input"))
    )
    (net (code "132") (name "unconnected-(U1-SCLK-Pad14)") (class "Default")
      (node (ref "U1") (pin "14") (pinfunction "SCLK_14") (pintype "input"))
    )
    (net (code "133") (name "unconnected-(U1-TXD-Pad22)") (class "Default")
      (node (ref "U1") (pin "22") (pinfunction "TXD_22") (pintype "output"))
    )
    (net (code "134") (name "unconnected-(U4-ADC6-Pad19)") (class "Default")
      (node (ref "U4") (pin "19") (pinfunction "ADC6_19") (pintype "bidirectional"))
    )
    (net (code "135") (name "unconnected-(U4-ADC7-Pad22)") (class "Default")
      (node (ref "U4") (pin "22") (pinfunction "ADC7_22") (pintype "bidirectional"))
    )
    (net (code "136") (name "unconnected-(U4-AREF-Pad20)") (class "Default")
      (node (ref "U4") (pin "20") (pinfunction "AREF_20") (pintype "input"))
    )
    (net (code "137") (name "unconnected-(U4-PB0-Pad12)") (class "Default")
      (node (ref "U4") (pin "12") (pinfunction "PB0_12") (pintype "bidirectional"))
    )
    (net (code "138") (name "unconnected-(U4-PB1-Pad13)") (class "Default")
      (node (ref "U4") (pin "13") (pinfunction "PB1_13") (pintype "bidirectional"))
    )
    (net (code "139") (name "unconnected-(U4-PC0-Pad23)") (class "Default")
      (node (ref "U4") (pin "23") (pinfunction "PC0_23") (pintype "bidirectional"))
    )
    (net (code "140") (name "unconnected-(U4-PC1-Pad24)") (class "Default")
      (node (ref "U4") (pin "24") (pinfunction "PC1_24") (pintype "bidirectional"))
    )
    (net (code "141") (name "unconnected-(U4-PC4-Pad27)") (class "Default")
      (node (ref "U4") (pin "27") (pinfunction "PC4_27") (pintype "bidirectional"))
    )
    (net (code "142") (name "unconnected-(U4-PC5-Pad28)") (class "Default")
      (node (ref "U4") (pin "28") (pinfunction "PC5_28") (pintype "bidirectional"))
    )
    (net (code "143") (name "unconnected-(U4-PD0-Pad30)") (class "Default")
      (node (ref "U4") (pin "30") (pinfunction "PD0_30") (pintype "bidirectional"))
    )
    (net (code "144") (name "unconnected-(U4-PD1-Pad31)") (class "Default")
      (node (ref "U4") (pin "31") (pinfunction "PD1_31") (pintype "bidirectional"))
    )
    (net (code "145") (name "unconnected-(U4-PD3-Pad1)") (class "Default")
      (node (ref "U4") (pin "1") (pinfunction "PD3_1") (pintype "bidirectional"))
    )
    (net (code "146") (name "unconnected-(U4-PD5-Pad9)") (class "Default")
      (node (ref "U4") (pin "9") (pinfunction "PD5_9") (pintype "bidirectional"))
    )
    (net (code "147") (name "unconnected-(U4-PD6-Pad10)") (class "Default")
      (node (ref "U4") (pin "10") (pinfunction "PD6_10") (pintype "bidirectional"))
    )
    (net (code "148") (name "unconnected-(U5-ADC6-Pad19)") (class "Default")
      (node (ref "U5") (pin "19") (pinfunction "ADC6_19") (pintype "bidirectional"))
    )
    (net (code "149") (name "unconnected-(U5-ADC7-Pad22)") (class "Default")
      (node (ref "U5") (pin "22") (pinfunction "ADC7_22") (pintype "bidirectional"))
    )
    (net (code "150") (name "unconnected-(U5-AREF-Pad20)") (class "Default")
      (node (ref "U5") (pin "20") (pinfunction "AREF_20") (pintype "input"))
    )
    (net (code "151") (name "unconnected-(U5-PB6-Pad7)") (class "Default")
      (node (ref "U5") (pin "7") (pinfunction "PB6_7") (pintype "bidirectional"))
    )
    (net (code "152") (name "unconnected-(U5-PB7-Pad8)") (class "Default")
      (node (ref "U5") (pin "8") (pinfunction "PB7_8") (pintype "bidirectional"))
    )
    (net (code "153") (name "unconnected-(U5-PC0-Pad23)") (class "Default")
      (node (ref "U5") (pin "23") (pinfunction "PC0_23") (pintype "bidirectional"))
    )
    (net (code "154") (name "unconnected-(U5-PC1-Pad24)") (class "Default")
      (node (ref "U5") (pin "24") (pinfunction "PC1_24") (pintype "bidirectional"))
    )
    (net (code "155") (name "unconnected-(U5-PC2-Pad25)") (class "Default")
      (node (ref "U5") (pin "25") (pinfunction "PC2_25") (pintype "bidirectional"))
    )
    (net (code "156") (name "unconnected-(U5-PC3-Pad26)") (class "Default")
      (node (ref "U5") (pin "26") (pinfunction "PC3_26") (pintype "bidirectional"))
    )
    (net (code "157") (name "unconnected-(U5-PC4-Pad27)") (class "Default")
      (node (ref "U5") (pin "27") (pinfunction "PC4_27") (pintype "bidirectional"))
    )
    (net (code "158") (name "unconnected-(U5-PC5-Pad28)") (class "Default")
      (node (ref "U5") (pin "28") (pinfunction "PC5_28") (pintype "bidirectional"))
    )
    (net (code "159") (name "unconnected-(U5-PC6{slash}~{RESET}-Pad29)") (class "Default")
      (node (ref "U5") (pin "29") (pinfunction "PC6/~{RESET}_29") (pintype "bidirectional"))
    )
    (net (code "160") (name "unconnected-(U5-PD3-Pad1)") (class "Default")
      (node (ref "U5") (pin "1") (pinfunction "PD3_1") (pintype "bidirectional"))
    )
    (net (code "161") (name "unconnected-(U5-PD4-Pad2)") (class "Default")
      (node (ref "U5") (pin "2") (pinfunction "PD4_2") (pintype "bidirectional"))
    )
    (net (code "162") (name "unconnected-(U5-PD5-Pad9)") (class "Default")
      (node (ref "U5") (pin "9") (pinfunction "PD5_9") (pintype "bidirectional"))
    )
    (net (code "163") (name "unconnected-(U5-PD6-Pad10)") (class "Default")
      (node (ref "U5") (pin "10") (pinfunction "PD6_10") (pintype "bidirectional"))
    )
    (net (code "164") (name "unconnected-(U5-PD7-Pad11)") (class "Default")
      (node (ref "U5") (pin "11") (pinfunction "PD7_11") (pintype "bidirectional"))
    )
  )
)
